# 2_AT_START_F403A_V1_2_MCU.net
KiCad netlist of a schematic drawn in Altium Designer
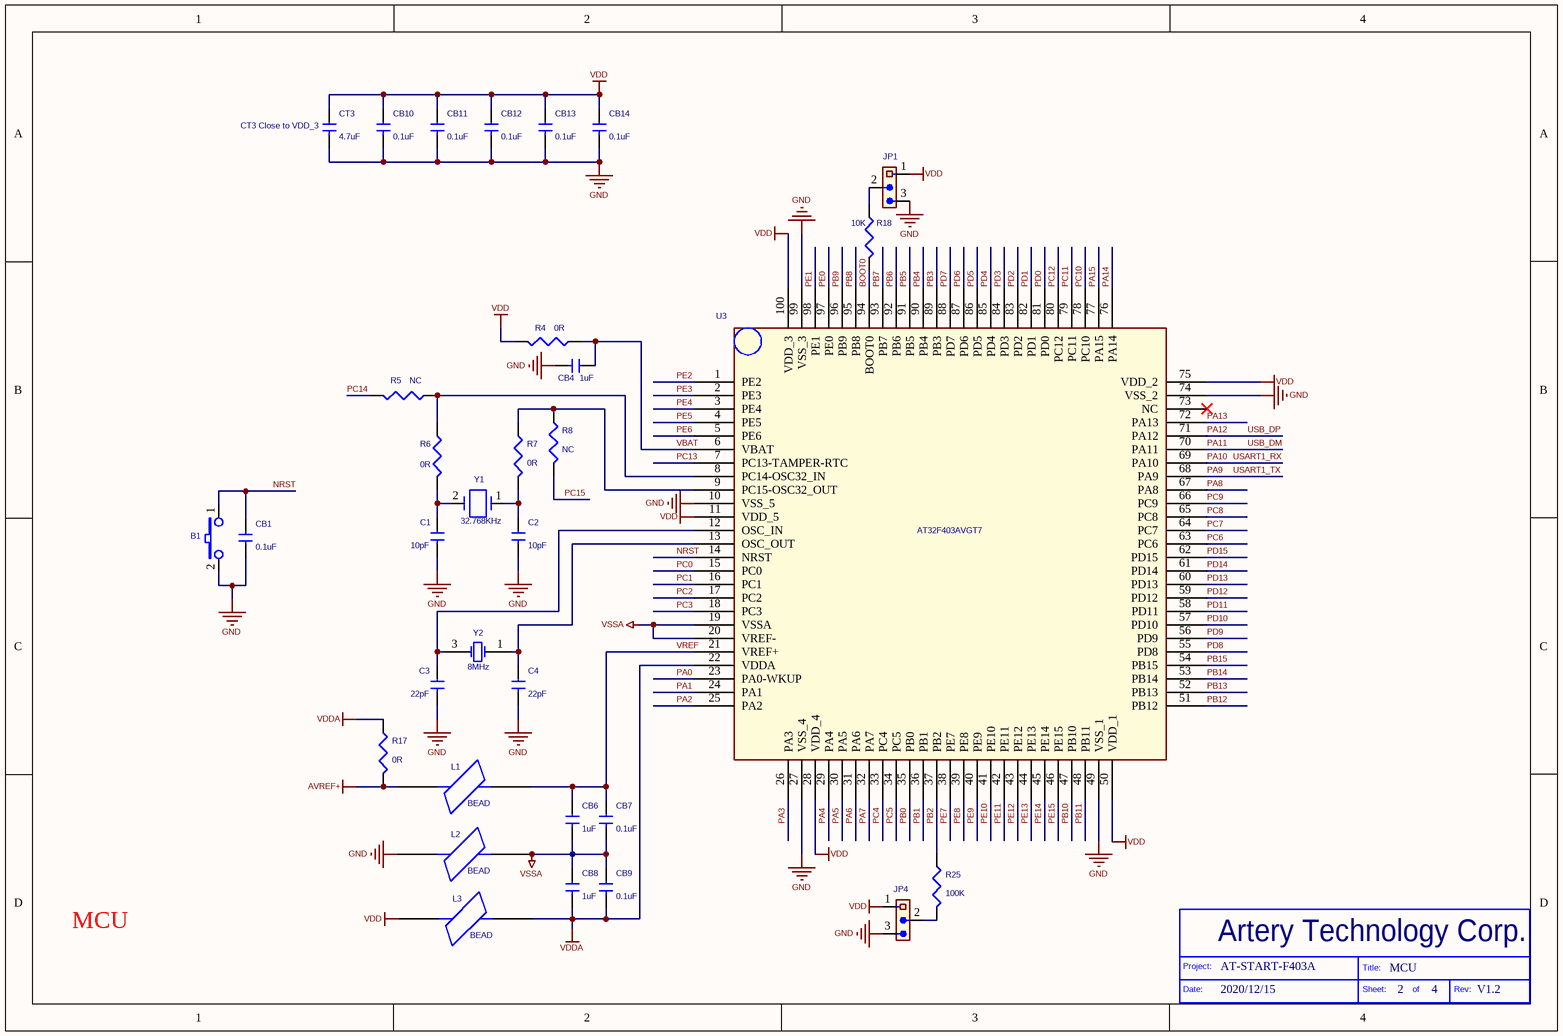
[diagram p0: 2_AT_START_F403A_V1.2_MCU.SchDoc]

(export (version "E")
  (design (tool "Eeschema 10.0.6"))
  (components
    (comp (ref "B1") (value "PB,BLACK,SMD_2P") (libsource (lib "*") (part "Push_Bottom,Blue,SMD_2P")))
    (comp (ref "C1") (value "10pF") (libsource (lib "*") (part "10pF,50V,5%,SMD0603")))
    (comp (ref "C2") (value "10pF") (libsource (lib "*") (part "10pF,50V,5%,SMD0603")))
    (comp (ref "C3") (value "22pF") (libsource (lib "*") (part "10pF,50V,5%,SMD0603")))
    (comp (ref "C4") (value "22pF") (libsource (lib "*") (part "10pF,50V,5%,SMD0603")))
    (comp (ref "CB1") (value "0.1uF") (libsource (lib "*") (part "0.1uF,50V,20%,SMD0603")))
    (comp (ref "CB4") (value "1uF") (libsource (lib "*") (part "0.1uF,50V,20%,SMD0603")))
    (comp (ref "CB6") (value "1uF") (libsource (lib "*") (part "0.1uF,50V,20%,SMD0603")))
    (comp (ref "CB7") (value "0.1uF") (libsource (lib "*") (part "0.1uF,50V,20%,SMD0603")))
    (comp (ref "CB8") (value "1uF") (libsource (lib "*") (part "0.1uF,50V,20%,SMD0603")))
    (comp (ref "CB9") (value "0.1uF") (libsource (lib "*") (part "0.1uF,50V,20%,SMD0603")))
    (comp (ref "CB10") (value "0.1uF") (libsource (lib "*") (part "0.1uF,25V,20%,SMD0402")))
    (comp (ref "CB11") (value "0.1uF") (libsource (lib "*") (part "0.1uF,25V,20%,SMD0402")))
    (comp (ref "CB12") (value "0.1uF") (libsource (lib "*") (part "0.1uF,25V,20%,SMD0402")))
    (comp (ref "CB13") (value "0.1uF") (libsource (lib "*") (part "0.1uF,25V,20%,SMD0402")))
    (comp (ref "CB14") (value "0.1uF") (libsource (lib "*") (part "0.1uF,25V,20%,SMD0402")))
    (comp (ref "CT3") (value "4.7uF") (libsource (lib "*") (part "0.1uF,25V,20%,SMD0402")))
    (comp (ref "JP1") (value "1X3P_2.54M") (libsource (lib "*") (part "1X3P,Male,DIP_2.54")))
    (comp (ref "JP4") (value "1X3P_2.54M") (libsource (lib "") (part "1X3P,Male,DIP_2.54_1")))
    (comp (ref "L1") (value "BEAD") (libsource (lib "*") (part "BEAD")))
    (comp (ref "L2") (value "BEAD") (libsource (lib "*") (part "BEAD")))
    (comp (ref "L3") (value "BEAD") (libsource (lib "*") (part "BEAD")))
    (comp (ref "R4") (value "0R") (libsource (lib "*") (part "470,1/10W,1%,SMD0603")))
    (comp (ref "R5") (value "NC") (libsource (lib "*") (part "0,1/10W,1%,SMD0603")))
    (comp (ref "R6") (value "0R") (libsource (lib "*") (part "0,1/10W,1%,SMD0603")))
    (comp (ref "R7") (value "0R") (libsource (lib "*") (part "0,1/10W,1%,SMD0603")))
    (comp (ref "R8") (value "NC") (libsource (lib "*") (part "0,1/10W,1%,SMD0603")))
    (comp (ref "R17") (value "0R") (libsource (lib "*") (part "470,1/10W,1%,SMD0603")))
    (comp (ref "R18") (value "10K") (libsource (lib "*") (part "10K,1/10W,1%,SMD0603")))
    (comp (ref "R25") (value "100K") (libsource (lib "*") (part "10K,1/10W,1%,SMD0603")))
    (comp (ref "U3")
      (value "AT32F403AVGT7")
      (footprint "LQFP100_14*14")
      (libsource (lib "ALL-Package") (part "LQFP100"))
    )
    (comp (ref "Y1")
      (value "32.768KHz")
      (description "FC-12M 2012 EPSON")
      (libsource (lib "*") (part "32.768KHz,CRY,30PPM,Size_3X8"))
    )
    (comp (ref "Y2")
      (value "8MHz")
      (footprint "SMD_5032_4P")
      (description "?片晶振")
      (libsource (lib "Artery_Wanbing") (part "SMD-5032_4P  8MHZ 20PF 10PPM"))
    )
  )
  (nets
    (net (code "1") (name "/BOOT0") (class "Default")
      (node (ref "R18") (pin "2") (pinfunction "2_2") (pintype "passive"))
      (node (ref "U3") (pin "94") (pinfunction "BOOT0_94") (pintype "passive"))
    )
    (net (code "2") (name "/NRST") (class "Default")
      (node (ref "B1") (pin "1") (pinfunction "1_1") (pintype "passive"))
      (node (ref "CB1") (pin "1") (pinfunction "1_1") (pintype "passive"))
      (node (ref "U3") (pin "14") (pinfunction "NRST_14") (pintype "passive"))
    )
    (net (code "3") (name "/PA0") (class "Default")
      (node (ref "U3") (pin "23") (pinfunction "PA0-WKUP_23") (pintype "passive"))
    )
    (net (code "4") (name "/PA1") (class "Default")
      (node (ref "U3") (pin "24") (pinfunction "PA1_24") (pintype "passive"))
    )
    (net (code "5") (name "/PA2") (class "Default")
      (node (ref "U3") (pin "25") (pinfunction "PA2_25") (pintype "passive"))
    )
    (net (code "6") (name "/PA3") (class "Default")
      (node (ref "U3") (pin "26") (pinfunction "PA3_26") (pintype "passive"))
    )
    (net (code "7") (name "/PA4") (class "Default")
      (node (ref "U3") (pin "29") (pinfunction "PA4_29") (pintype "passive"))
    )
    (net (code "8") (name "/PA5") (class "Default")
      (node (ref "U3") (pin "30") (pinfunction "PA5_30") (pintype "passive"))
    )
    (net (code "9") (name "/PA6") (class "Default")
      (node (ref "U3") (pin "31") (pinfunction "PA6_31") (pintype "passive"))
    )
    (net (code "10") (name "/PA7") (class "Default")
      (node (ref "U3") (pin "32") (pinfunction "PA7_32") (pintype "passive"))
    )
    (net (code "11") (name "/PA8") (class "Default")
      (node (ref "U3") (pin "67") (pinfunction "PA8_67") (pintype "passive"))
    )
    (net (code "12") (name "/PA9") (class "Default")
      (node (ref "U3") (pin "68") (pinfunction "PA9_68") (pintype "passive"))
    )
    (net (code "13") (name "/PA10") (class "Default")
      (node (ref "U3") (pin "69") (pinfunction "PA10_69") (pintype "passive"))
    )
    (net (code "14") (name "/PA11") (class "Default")
      (node (ref "U3") (pin "70") (pinfunction "PA11_70") (pintype "passive"))
    )
    (net (code "15") (name "/PA12") (class "Default")
      (node (ref "U3") (pin "71") (pinfunction "PA12_71") (pintype "passive"))
    )
    (net (code "16") (name "/PA13") (class "Default")
      (node (ref "U3") (pin "72") (pinfunction "PA13_72") (pintype "passive"))
    )
    (net (code "17") (name "/PA14") (class "Default")
      (node (ref "U3") (pin "76") (pinfunction "PA14_76") (pintype "passive"))
    )
    (net (code "18") (name "/PA15") (class "Default")
      (node (ref "U3") (pin "77") (pinfunction "PA15_77") (pintype "passive"))
    )
    (net (code "19") (name "/PB0") (class "Default")
      (node (ref "U3") (pin "35") (pinfunction "PB0_35") (pintype "passive"))
    )
    (net (code "20") (name "/PB1") (class "Default")
      (node (ref "U3") (pin "36") (pinfunction "PB1_36") (pintype "passive"))
    )
    (net (code "21") (name "/PB2") (class "Default")
      (node (ref "R25") (pin "1") (pinfunction "1_1") (pintype "passive"))
      (node (ref "U3") (pin "37") (pinfunction "PB2_37") (pintype "passive"))
    )
    (net (code "22") (name "/PB3") (class "Default")
      (node (ref "U3") (pin "89") (pinfunction "PB3_89") (pintype "passive"))
    )
    (net (code "23") (name "/PB4") (class "Default")
      (node (ref "U3") (pin "90") (pinfunction "PB4_90") (pintype "passive"))
    )
    (net (code "24") (name "/PB5") (class "Default")
      (node (ref "U3") (pin "91") (pinfunction "PB5_91") (pintype "passive"))
    )
    (net (code "25") (name "/PB6") (class "Default")
      (node (ref "U3") (pin "92") (pinfunction "PB6_92") (pintype "passive"))
    )
    (net (code "26") (name "/PB7") (class "Default")
      (node (ref "U3") (pin "93") (pinfunction "PB7_93") (pintype "passive"))
    )
    (net (code "27") (name "/PB8") (class "Default")
      (node (ref "U3") (pin "95") (pinfunction "PB8_95") (pintype "passive"))
    )
    (net (code "28") (name "/PB9") (class "Default")
      (node (ref "U3") (pin "96") (pinfunction "PB9_96") (pintype "passive"))
    )
    (net (code "29") (name "/PB10") (class "Default")
      (node (ref "U3") (pin "47") (pinfunction "PB10_47") (pintype "passive"))
    )
    (net (code "30") (name "/PB11") (class "Default")
      (node (ref "U3") (pin "48") (pinfunction "PB11_48") (pintype "passive"))
    )
    (net (code "31") (name "/PB12") (class "Default")
      (node (ref "U3") (pin "51") (pinfunction "PB12_51") (pintype "passive"))
    )
    (net (code "32") (name "/PB13") (class "Default")
      (node (ref "U3") (pin "52") (pinfunction "PB13_52") (pintype "passive"))
    )
    (net (code "33") (name "/PB14") (class "Default")
      (node (ref "U3") (pin "53") (pinfunction "PB14_53") (pintype "passive"))
    )
    (net (code "34") (name "/PB15") (class "Default")
      (node (ref "U3") (pin "54") (pinfunction "PB15_54") (pintype "passive"))
    )
    (net (code "35") (name "/PC0") (class "Default")
      (node (ref "U3") (pin "15") (pinfunction "PC0_15") (pintype "passive"))
    )
    (net (code "36") (name "/PC1") (class "Default")
      (node (ref "U3") (pin "16") (pinfunction "PC1_16") (pintype "passive"))
    )
    (net (code "37") (name "/PC2") (class "Default")
      (node (ref "U3") (pin "17") (pinfunction "PC2_17") (pintype "passive"))
    )
    (net (code "38") (name "/PC3") (class "Default")
      (node (ref "U3") (pin "18") (pinfunction "PC3_18") (pintype "passive"))
    )
    (net (code "39") (name "/PC4") (class "Default")
      (node (ref "U3") (pin "33") (pinfunction "PC4_33") (pintype "passive"))
    )
    (net (code "40") (name "/PC5") (class "Default")
      (node (ref "U3") (pin "34") (pinfunction "PC5_34") (pintype "passive"))
    )
    (net (code "41") (name "/PC6") (class "Default")
      (node (ref "U3") (pin "63") (pinfunction "PC6_63") (pintype "passive"))
    )
    (net (code "42") (name "/PC7") (class "Default")
      (node (ref "U3") (pin "64") (pinfunction "PC7_64") (pintype "passive"))
    )
    (net (code "43") (name "/PC8") (class "Default")
      (node (ref "U3") (pin "65") (pinfunction "PC8_65") (pintype "passive"))
    )
    (net (code "44") (name "/PC9") (class "Default")
      (node (ref "U3") (pin "66") (pinfunction "PC9_66") (pintype "passive"))
    )
    (net (code "45") (name "/PC10") (class "Default")
      (node (ref "U3") (pin "78") (pinfunction "PC10_78") (pintype "passive"))
    )
    (net (code "46") (name "/PC11") (class "Default")
      (node (ref "U3") (pin "79") (pinfunction "PC11_79") (pintype "passive"))
    )
    (net (code "47") (name "/PC12") (class "Default")
      (node (ref "U3") (pin "80") (pinfunction "PC12_80") (pintype "passive"))
    )
    (net (code "48") (name "/PC13") (class "Default")
      (node (ref "U3") (pin "7") (pinfunction "PC13-TAMPER-RTC_7") (pintype "passive"))
    )
    (net (code "49") (name "/PC14") (class "Default")
      (node (ref "R5") (pin "2") (pinfunction "2_2") (pintype "passive"))
    )
    (net (code "50") (name "/PC15") (class "Default")
      (node (ref "R8") (pin "2") (pinfunction "2_2") (pintype "passive"))
    )
    (net (code "51") (name "/PD0") (class "Default")
      (node (ref "U3") (pin "81") (pinfunction "PD0_81") (pintype "passive"))
    )
    (net (code "52") (name "/PD1") (class "Default")
      (node (ref "U3") (pin "82") (pinfunction "PD1_82") (pintype "passive"))
    )
    (net (code "53") (name "/PD2") (class "Default")
      (node (ref "U3") (pin "83") (pinfunction "PD2_83") (pintype "passive"))
    )
    (net (code "54") (name "/PD3") (class "Default")
      (node (ref "U3") (pin "84") (pinfunction "PD3_84") (pintype "passive"))
    )
    (net (code "55") (name "/PD4") (class "Default")
      (node (ref "U3") (pin "85") (pinfunction "PD4_85") (pintype "passive"))
    )
    (net (code "56") (name "/PD5") (class "Default")
      (node (ref "U3") (pin "86") (pinfunction "PD5_86") (pintype "passive"))
    )
    (net (code "57") (name "/PD6") (class "Default")
      (node (ref "U3") (pin "87") (pinfunction "PD6_87") (pintype "passive"))
    )
    (net (code "58") (name "/PD7") (class "Default")
      (node (ref "U3") (pin "88") (pinfunction "PD7_88") (pintype "passive"))
    )
    (net (code "59") (name "/PD8") (class "Default")
      (node (ref "U3") (pin "55") (pinfunction "PD8_55") (pintype "passive"))
    )
    (net (code "60") (name "/PD9") (class "Default")
      (node (ref "U3") (pin "56") (pinfunction "PD9_56") (pintype "passive"))
    )
    (net (code "61") (name "/PD10") (class "Default")
      (node (ref "U3") (pin "57") (pinfunction "PD10_57") (pintype "passive"))
    )
    (net (code "62") (name "/PD11") (class "Default")
      (node (ref "U3") (pin "58") (pinfunction "PD11_58") (pintype "passive"))
    )
    (net (code "63") (name "/PD12") (class "Default")
      (node (ref "U3") (pin "59") (pinfunction "PD12_59") (pintype "passive"))
    )
    (net (code "64") (name "/PD13") (class "Default")
      (node (ref "U3") (pin "60") (pinfunction "PD13_60") (pintype "passive"))
    )
    (net (code "65") (name "/PD14") (class "Default")
      (node (ref "U3") (pin "61") (pinfunction "PD14_61") (pintype "passive"))
    )
    (net (code "66") (name "/PD15") (class "Default")
      (node (ref "U3") (pin "62") (pinfunction "PD15_62") (pintype "passive"))
    )
    (net (code "67") (name "/PE0") (class "Default")
      (node (ref "U3") (pin "97") (pinfunction "PE0_97") (pintype "passive"))
    )
    (net (code "68") (name "/PE1") (class "Default")
      (node (ref "U3") (pin "98") (pinfunction "PE1_98") (pintype "passive"))
    )
    (net (code "69") (name "/PE2") (class "Default")
      (node (ref "U3") (pin "1") (pinfunction "PE2_1") (pintype "passive"))
    )
    (net (code "70") (name "/PE3") (class "Default")
      (node (ref "U3") (pin "2") (pinfunction "PE3_2") (pintype "passive"))
    )
    (net (code "71") (name "/PE4") (class "Default")
      (node (ref "U3") (pin "3") (pinfunction "PE4_3") (pintype "passive"))
    )
    (net (code "72") (name "/PE5") (class "Default")
      (node (ref "U3") (pin "4") (pinfunction "PE5_4") (pintype "passive"))
    )
    (net (code "73") (name "/PE6") (class "Default")
      (node (ref "U3") (pin "5") (pinfunction "PE6_5") (pintype "passive"))
    )
    (net (code "74") (name "/PE7") (class "Default")
      (node (ref "U3") (pin "38") (pinfunction "PE7_38") (pintype "passive"))
    )
    (net (code "75") (name "/PE8") (class "Default")
      (node (ref "U3") (pin "39") (pinfunction "PE8_39") (pintype "passive"))
    )
    (net (code "76") (name "/PE9") (class "Default")
      (node (ref "U3") (pin "40") (pinfunction "PE9_40") (pintype "passive"))
    )
    (net (code "77") (name "/PE10") (class "Default")
      (node (ref "U3") (pin "41") (pinfunction "PE10_41") (pintype "passive"))
    )
    (net (code "78") (name "/PE11") (class "Default")
      (node (ref "U3") (pin "42") (pinfunction "PE11_42") (pintype "passive"))
    )
    (net (code "79") (name "/PE12") (class "Default")
      (node (ref "U3") (pin "43") (pinfunction "PE12_43") (pintype "passive"))
    )
    (net (code "80") (name "/PE13") (class "Default")
      (node (ref "U3") (pin "44") (pinfunction "PE13_44") (pintype "passive"))
    )
    (net (code "81") (name "/PE14") (class "Default")
      (node (ref "U3") (pin "45") (pinfunction "PE14_45") (pintype "passive"))
    )
    (net (code "82") (name "/PE15") (class "Default")
      (node (ref "U3") (pin "46") (pinfunction "PE15_46") (pintype "passive"))
    )
    (net (code "83") (name "/VBAT") (class "Default")
      (node (ref "CB4") (pin "1") (pinfunction "1_1") (pintype "passive"))
      (node (ref "R4") (pin "1") (pinfunction "1_1") (pintype "passive"))
      (node (ref "U3") (pin "6") (pinfunction "VBAT_6") (pintype "passive"))
    )
    (net (code "84") (name "/VREF") (class "Default")
      (node (ref "CB6") (pin "1") (pinfunction "1_1") (pintype "passive"))
      (node (ref "CB7") (pin "1") (pinfunction "1_1") (pintype "passive"))
      (node (ref "L1") (pin "2") (pinfunction "2_2") (pintype "passive"))
      (node (ref "U3") (pin "21") (pinfunction "VREF+_21") (pintype "passive"))
    )
    (net (code "85") (name "AVREF+") (class "Default")
      (node (ref "L1") (pin "1") (pinfunction "1_1") (pintype "passive"))
      (node (ref "R17") (pin "2") (pinfunction "2_2") (pintype "passive"))
    )
    (net (code "86") (name "GND") (class "Default")
      (node (ref "B1") (pin "2") (pinfunction "2_2") (pintype "passive"))
      (node (ref "C1") (pin "2") (pinfunction "2_2") (pintype "passive"))
      (node (ref "C2") (pin "2") (pinfunction "2_2") (pintype "passive"))
      (node (ref "C3") (pin "2") (pinfunction "2_2") (pintype "passive"))
      (node (ref "C4") (pin "2") (pinfunction "2_2") (pintype "passive"))
      (node (ref "CB1") (pin "2") (pinfunction "2_2") (pintype "passive"))
      (node (ref "CB10") (pin "2") (pinfunction "2_2") (pintype "passive"))
      (node (ref "CB11") (pin "2") (pinfunction "2_2") (pintype "passive"))
      (node (ref "CB12") (pin "2") (pinfunction "2_2") (pintype "passive"))
      (node (ref "CB13") (pin "2") (pinfunction "2_2") (pintype "passive"))
      (node (ref "CB14") (pin "2") (pinfunction "2_2") (pintype "passive"))
      (node (ref "CB4") (pin "2") (pinfunction "2_2") (pintype "passive"))
      (node (ref "CT3") (pin "2") (pinfunction "2_2") (pintype "passive"))
      (node (ref "JP1") (pin "3") (pinfunction "3_3") (pintype "passive"))
      (node (ref "JP4") (pin "3") (pinfunction "3_3") (pintype "passive"))
      (node (ref "L2") (pin "1") (pinfunction "1_1") (pintype "passive"))
      (node (ref "U3") (pin "10") (pinfunction "VSS_5_10") (pintype "passive"))
      (node (ref "U3") (pin "27") (pinfunction "VSS_4_27") (pintype "passive"))
      (node (ref "U3") (pin "49") (pinfunction "VSS_1_49") (pintype "passive"))
      (node (ref "U3") (pin "74") (pinfunction "VSS_2_74") (pintype "passive"))
      (node (ref "U3") (pin "99") (pinfunction "VSS_3_99") (pintype "passive"))
    )
    (net (code "87") (name "Net-(C1-Pad1)") (class "Default")
      (node (ref "C1") (pin "1") (pinfunction "1_1") (pintype "passive"))
      (node (ref "R6") (pin "2") (pinfunction "2_2") (pintype "passive"))
      (node (ref "Y1") (pin "2") (pinfunction "2_2") (pintype "passive"))
    )
    (net (code "88") (name "Net-(C2-Pad1)") (class "Default")
      (node (ref "C2") (pin "1") (pinfunction "1_1") (pintype "passive"))
      (node (ref "R7") (pin "2") (pinfunction "2_2") (pintype "passive"))
      (node (ref "Y1") (pin "1") (pinfunction "1_1") (pintype "passive"))
    )
    (net (code "89") (name "Net-(JP1-Pad2)") (class "Default")
      (node (ref "JP1") (pin "2") (pinfunction "2_2") (pintype "passive"))
      (node (ref "R18") (pin "1") (pinfunction "1_1") (pintype "passive"))
    )
    (net (code "90") (name "Net-(JP4-Pad2)") (class "Default")
      (node (ref "JP4") (pin "2") (pinfunction "2_2") (pintype "passive"))
      (node (ref "R25") (pin "2") (pinfunction "2_2") (pintype "passive"))
    )
    (net (code "91") (name "Net-(U3-OSC_IN)") (class "Default")
      (node (ref "C3") (pin "1") (pinfunction "1_1") (pintype "passive"))
      (node (ref "U3") (pin "12") (pinfunction "OSC_IN_12") (pintype "passive"))
      (node (ref "Y2") (pin "3") (pinfunction "OSC2_3") (pintype "passive"))
    )
    (net (code "92") (name "Net-(U3-OSC_OUT)") (class "Default")
      (node (ref "C4") (pin "1") (pinfunction "1_1") (pintype "passive"))
      (node (ref "U3") (pin "13") (pinfunction "OSC_OUT_13") (pintype "passive"))
      (node (ref "Y2") (pin "1") (pinfunction "OSC1_1") (pintype "passive"))
    )
    (net (code "93") (name "Net-(U3-PC14-OSC32_IN)") (class "Default")
      (node (ref "R5") (pin "1") (pinfunction "1_1") (pintype "passive"))
      (node (ref "R6") (pin "1") (pinfunction "1_1") (pintype "passive"))
      (node (ref "U3") (pin "8") (pinfunction "PC14-OSC32_IN_8") (pintype "passive"))
    )
    (net (code "94") (name "Net-(U3-PC15-OSC32_OUT)") (class "Default")
      (node (ref "R7") (pin "1") (pinfunction "1_1") (pintype "passive"))
      (node (ref "R8") (pin "1") (pinfunction "1_1") (pintype "passive"))
      (node (ref "U3") (pin "9") (pinfunction "PC15-OSC32_OUT_9") (pintype "passive"))
    )
    (net (code "95") (name "VDD") (class "Default")
      (node (ref "CB10") (pin "1") (pinfunction "1_1") (pintype "passive"))
      (node (ref "CB11") (pin "1") (pinfunction "1_1") (pintype "passive"))
      (node (ref "CB12") (pin "1") (pinfunction "1_1") (pintype "passive"))
      (node (ref "CB13") (pin "1") (pinfunction "1_1") (pintype "passive"))
      (node (ref "CB14") (pin "1") (pinfunction "1_1") (pintype "passive"))
      (node (ref "CT3") (pin "1") (pinfunction "1_1") (pintype "passive"))
      (node (ref "JP1") (pin "1") (pinfunction "1_1") (pintype "passive"))
      (node (ref "JP4") (pin "1") (pinfunction "1_1") (pintype "passive"))
      (node (ref "L3") (pin "1") (pinfunction "1_1") (pintype "passive"))
      (node (ref "R4") (pin "2") (pinfunction "2_2") (pintype "passive"))
      (node (ref "U3") (pin "100") (pinfunction "VDD_3_100") (pintype "passive"))
      (node (ref "U3") (pin "11") (pinfunction "VDD_5_11") (pintype "passive"))
      (node (ref "U3") (pin "28") (pinfunction "VDD_4_28") (pintype "passive"))
      (node (ref "U3") (pin "50") (pinfunction "VDD_1_50") (pintype "passive"))
      (node (ref "U3") (pin "75") (pinfunction "VDD_2_75") (pintype "passive"))
    )
    (net (code "96") (name "VDDA") (class "Default")
      (node (ref "CB8") (pin "2") (pinfunction "2_2") (pintype "passive"))
      (node (ref "CB9") (pin "2") (pinfunction "2_2") (pintype "passive"))
      (node (ref "L3") (pin "2") (pinfunction "2_2") (pintype "passive"))
      (node (ref "R17") (pin "1") (pinfunction "1_1") (pintype "passive"))
      (node (ref "U3") (pin "22") (pinfunction "VDDA_22") (pintype "passive"))
    )
    (net (code "97") (name "VSSA") (class "Default")
      (node (ref "CB6") (pin "2") (pinfunction "2_2") (pintype "passive"))
      (node (ref "CB7") (pin "2") (pinfunction "2_2") (pintype "passive"))
      (node (ref "CB8") (pin "1") (pinfunction "1_1") (pintype "passive"))
      (node (ref "CB9") (pin "1") (pinfunction "1_1") (pintype "passive"))
      (node (ref "L2") (pin "2") (pinfunction "2_2") (pintype "passive"))
      (node (ref "U3") (pin "19") (pinfunction "VSSA_19") (pintype "passive"))
      (node (ref "U3") (pin "20") (pinfunction "VREF-_20") (pintype "passive"))
    )
    (net (code "98") (name "unconnected-(U3-NC-Pad73)") (class "Default")
      (node (ref "U3") (pin "73") (pinfunction "NC_73") (pintype "passive+no_connect"))
    )
  )
)
